# updated_sami_board_v2.net
KiCad netlist of a schematic drawn in Altium Designer
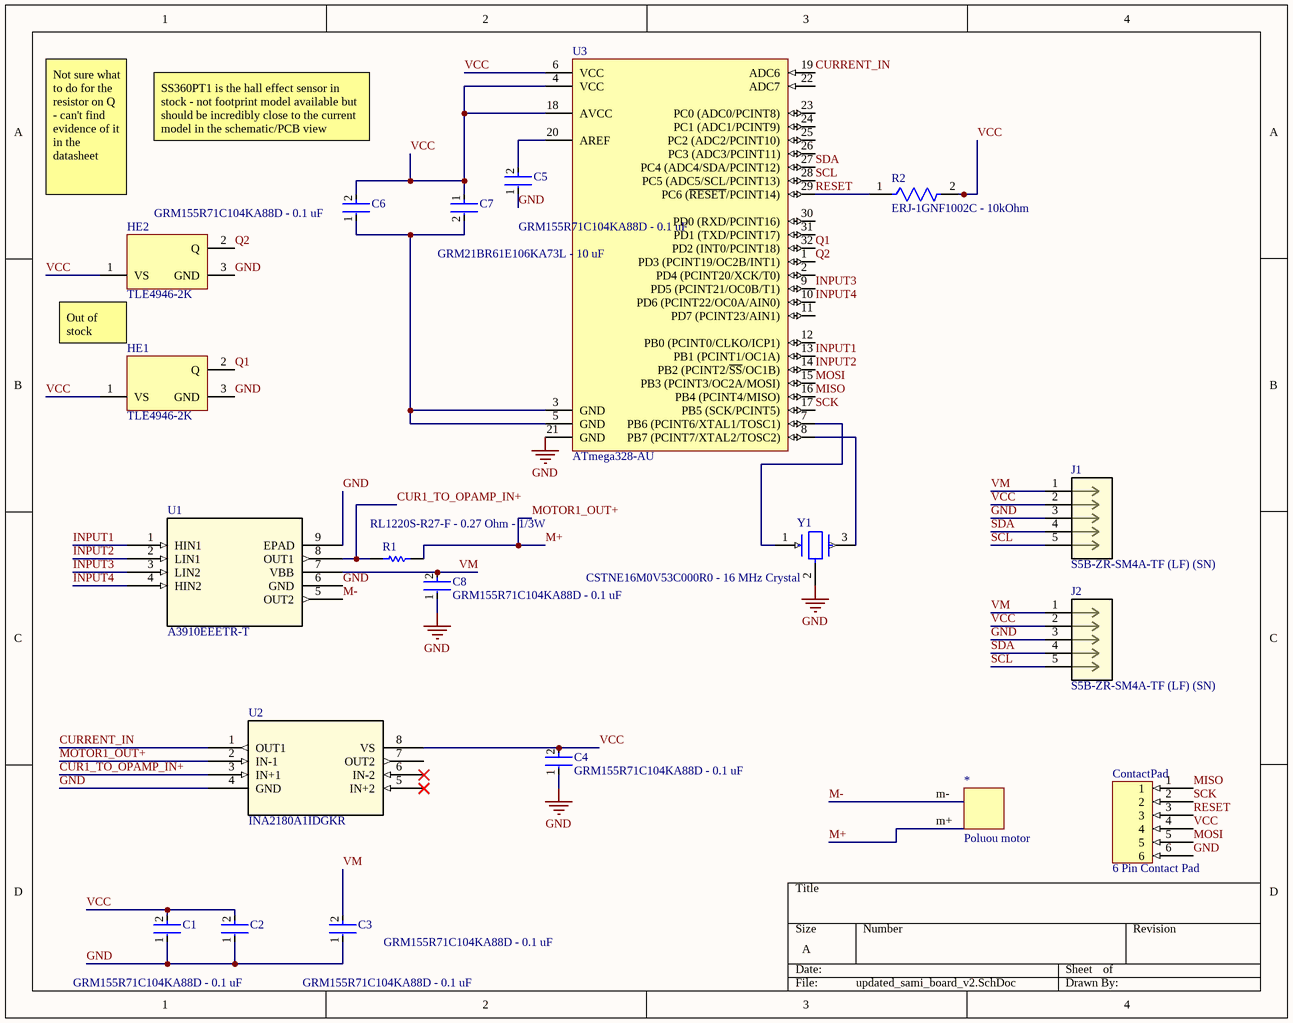
[diagram p0: updated_sami_board_v2.SchDoc]

(export (version "E")
  (design (tool "Eeschema 10.0.6"))
  (components
    (comp (ref "*")
      (value "Poluou motor")
      (footprint "PCBComponent_1")
      (libsource (lib "polulu_motor") (part "Poluou motor"))
    )
    (comp (ref "C1")
      (value "GRM155R71C104KA88D - 0.1 uF")
      (footprint "FP-GRM15-MFG")
      (description "CAP CER 0.1UF 16V X7R 0402")
      (fields (field (name "MANUFACTURER PART NUMBER") "GRM155R71C104KA88D") (field (name "TOLERANCE") "10%"))
      (libsource (lib "Altium Content Vault") (part "236180d848d6139a670b325ea6854c9"))
    )
    (comp (ref "C2")
      (value "GRM155R71C104KA88D - 0.1 uF")
      (footprint "FP-GRM15-MFG")
      (description "CAP CER 0.1UF 16V X7R 0402")
      (fields (field (name "MANUFACTURER PART NUMBER") "GRM155R71C104KA88D") (field (name "TOLERANCE") "10%"))
      (libsource (lib "Altium Content Vault") (part "236180d848d6139a670b325ea6854c9"))
    )
    (comp (ref "C3")
      (value "GRM155R71C104KA88D - 0.1 uF")
      (footprint "FP-GRM15-MFG")
      (description "CAP CER 0.1UF 16V X7R 0402")
      (fields (field (name "MANUFACTURER PART NUMBER") "GRM155R71C104KA88D") (field (name "TOLERANCE") "10%"))
      (libsource (lib "Altium Content Vault") (part "236180d848d6139a670b325ea6854c9"))
    )
    (comp (ref "C4")
      (value "GRM155R71C104KA88D - 0.1 uF")
      (footprint "FP-GRM15-MFG")
      (description "CAP CER 0.1UF 16V X7R 0402")
      (fields (field (name "MANUFACTURER PART NUMBER") "GRM155R71C104KA88D") (field (name "TOLERANCE") "10%"))
      (libsource (lib "Altium Content Vault") (part "236180d848d6139a670b325ea6854c9"))
    )
    (comp (ref "C5")
      (value "GRM155R71C104KA88D - 0.1 uF")
      (footprint "FP-GRM15-MFG")
      (description "CAP CER 0.1UF 16V X7R 0402")
      (fields (field (name "MANUFACTURER PART NUMBER") "GRM155R71C104KA88D") (field (name "TOLERANCE") "10%"))
      (libsource (lib "Altium Content Vault") (part "236180d848d6139a670b325ea6854c9"))
    )
    (comp (ref "C6")
      (value "GRM155R71C104KA88D - 0.1 uF")
      (footprint "FP-GRM15-MFG")
      (description "CAP CER 0.1UF 16V X7R 0402")
      (fields (field (name "MANUFACTURER PART NUMBER") "GRM155R71C104KA88D") (field (name "TOLERANCE") "10%"))
      (libsource (lib "Altium Content Vault") (part "236180d848d6139a670b325ea6854c9"))
    )
    (comp (ref "C7")
      (value "GRM21BR61E106KA73L - 10 uF")
      (footprint "FP-GRM21B-0_15-IPC_C")
      (description "Chip Multilayer Ceramic Capacitors for General Purpose, 0805, 10uF, X5R, 15%, 10%, 25V")
      (fields (field (name "VOLTAGE") "25V") (field (name "TOLERANCE") "10%"))
      (libsource (lib "Altium Content Vault") (part "b4654b650e69147ec39a6b967a45e02"))
    )
    (comp (ref "C8")
      (value "GRM155R71C104KA88D - 0.1 uF")
      (footprint "FP-GRM15-MFG")
      (description "CAP CER 0.1UF 16V X7R 0402")
      (fields (field (name "MANUFACTURER PART NUMBER") "GRM155R71C104KA88D") (field (name "TOLERANCE") "10%"))
      (libsource (lib "Altium Content Vault") (part "236180d848d6139a670b325ea6854c9"))
    )
    (comp (ref "ContactPad")
      (value "6 Pin Contact Pad")
      (footprint "6PinContactPad")
      (libsource (lib "6PinContactPad") (part "6 Pin Contact Pad"))
    )
    (comp (ref "HE1")
      (value "TLE4946-2K")
      (footprint "INF-PG-SC59_M")
      (description "High Precision Hall Effect Latch, PG-SC59, Reel, Green")
      (fields (field (name "MANUFACTURER") "Infineon"))
      (libsource (lib "Altium Content Vault") (part "INF-TLE49XX-SC59-3"))
    )
    (comp (ref "HE2")
      (value "TLE4946-2K")
      (footprint "INF-PG-SC59_M")
      (description "High Precision Hall Effect Latch, PG-SC59, Reel, Green")
      (fields (field (name "MANUFACTURER") "Infineon"))
      (libsource (lib "Altium Content Vault") (part "INF-TLE49XX-SC59-3"))
    )
    (comp (ref "J1")
      (value "S5B-ZR-SM4A-TF (LF) (SN)")
      (footprint "CONN_S5B-ZR-SM4A-TF_JST")
      (description "No Description Available")
      (fields (field (name "COPYRIGHT") "Copyright (C) 2021 Ultra Librarian. All rights reserved."))
      (libsource (lib "S5B-ZR-SM4A-TF_LF__SN_") (part "S5B-ZR-SM4A-TF (LF) (SN)"))
    )
    (comp (ref "J2")
      (value "S5B-ZR-SM4A-TF (LF) (SN)")
      (footprint "CONN_S5B-ZR-SM4A-TF_JST")
      (description "No Description Available")
      (fields (field (name "COPYRIGHT") "Copyright (C) 2021 Ultra Librarian. All rights reserved."))
      (libsource (lib "S5B-ZR-SM4A-TF_LF__SN_") (part "S5B-ZR-SM4A-TF (LF) (SN)"))
    )
    (comp (ref "R1")
      (value "RL1220S-R27-F - 0.27 Ohm - 1/3W")
      (footprint "RESC2013X50X40NL20T20")
      (fields (field (name "PART NUMBER") "RL1220S-R27-F") (field (name "MANUFACTURER") "Susumu"))
      (libsource (lib "Altium Content Vault") (part "RES"))
    )
    (comp (ref "R2")
      (value "ERJ-1GNF1002C - 10kOhm")
      (footprint "FP-ERJ1G-MFG")
      (description "RES SMD 10K OHM 1% 1/20W 0201")
      (fields
        (field (name "MANUFACTURER PART NUMBER") "ERJ-1GNF1002C")
        (field (name "OCTOPART") "https://octopart.com/erj-1gnf1002c-panasonic-55419697")
      )
      (libsource (lib "Altium Content Vault") (part "1029c3af85768c4190bb7ad29bc67b5"))
    )
    (comp (ref "U1")
      (value "A3910EEETR-T")
      (footprint "DFN-8_ALM")
      (description "No Description Available")
      (fields (field (name "COPYRIGHT") "Copyright (C) 2021 Ultra Librarian. All rights reserved."))
      (libsource (lib "A3910EEETR-T") (part "A3910EEETR-T"))
    )
    (comp (ref "U2")
      (value "INA2180A1IDGKR")
      (footprint "DGK8_TEX")
      (description "No Description Available")
      (fields (field (name "COPYRIGHT") "Copyright (C) 2021 Ultra Librarian. All rights reserved."))
      (libsource (lib "INA2180A1IDGKR") (part "INA2180A1IDGKR"))
    )
    (comp (ref "U3")
      (value "ATmega328-AU")
      (footprint "32A_L")
      (libsource (lib "Altium Content Vault") (part "MC-8B-ATM48-SQ32"))
    )
    (comp (ref "Y1")
      (value "CSTNE16M0V53C000R0 - 16 MHz Crystal")
      (footprint "FP-CSTNE16M0V53C000R0-MFG")
      (description "CERAMIC RES 16.0000MHZ 15PF SMD")
      (libsource (lib "Altium Content Vault") (part "7d37667f5012bb31280c8009ddd0b1c"))
    )
  )
  (nets
    (net (code "1") (name "/CUR1_TO_OPAMP_IN+") (class "Default")
      (node (ref "R1") (pin "1") (pinfunction "1_1") (pintype "passive"))
      (node (ref "U1") (pin "8") (pinfunction "OUT1_8") (pintype "output"))
      (node (ref "U2") (pin "3") (pinfunction "IN+1_3") (pintype "input"))
    )
    (net (code "2") (name "/CURRENT_IN") (class "Default")
      (node (ref "U2") (pin "1") (pinfunction "OUT1_1") (pintype "output"))
      (node (ref "U3") (pin "19") (pinfunction "ADC6_19") (pintype "input"))
    )
    (net (code "3") (name "/INPUT1") (class "Default")
      (node (ref "U1") (pin "1") (pinfunction "HIN1_1") (pintype "input"))
      (node (ref "U3") (pin "13") (pinfunction "PB1_(PCINT1/OC1A)_13") (pintype "bidirectional"))
    )
    (net (code "4") (name "/INPUT2") (class "Default")
      (node (ref "U1") (pin "2") (pinfunction "LIN1_2") (pintype "input"))
      (node (ref "U3") (pin "14") (pinfunction "PB2_(PCINT2/~{SS}/OC1B)_14") (pintype "bidirectional"))
    )
    (net (code "5") (name "/INPUT3") (class "Default")
      (node (ref "U1") (pin "3") (pinfunction "LIN2_3") (pintype "input"))
      (node (ref "U3") (pin "9") (pinfunction "PD5_(PCINT21/OC0B/T1)_9") (pintype "bidirectional"))
    )
    (net (code "6") (name "/INPUT4") (class "Default")
      (node (ref "U1") (pin "4") (pinfunction "HIN2_4") (pintype "input"))
      (node (ref "U3") (pin "10") (pinfunction "PD6_(PCINT22/OC0A/AIN0)_10") (pintype "bidirectional"))
    )
    (net (code "7") (name "/M+") (class "Default")
      (node (ref "*") (pin "m+") (pintype "passive"))
      (node (ref "R1") (pin "2") (pinfunction "2_2") (pintype "passive"))
      (node (ref "U2") (pin "2") (pinfunction "IN-1_2") (pintype "input"))
    )
    (net (code "8") (name "/M-") (class "Default")
      (node (ref "*") (pin "m-") (pintype "passive"))
      (node (ref "U1") (pin "5") (pinfunction "OUT2_5") (pintype "output"))
    )
    (net (code "9") (name "/MISO") (class "Default")
      (node (ref "ContactPad") (pin "1") (pinfunction "1_1") (pintype "input"))
      (node (ref "U3") (pin "16") (pinfunction "PB4_(PCINT4/MISO)_16") (pintype "bidirectional"))
    )
    (net (code "10") (name "/MOSI") (class "Default")
      (node (ref "ContactPad") (pin "5") (pinfunction "5_5") (pintype "input"))
      (node (ref "U3") (pin "15") (pinfunction "PB3_(PCINT3/OC2A/MOSI)_15") (pintype "bidirectional"))
    )
    (net (code "11") (name "/Q1") (class "Default")
      (node (ref "HE1") (pin "2") (pinfunction "Q_2") (pintype "open_collector"))
      (node (ref "U3") (pin "32") (pinfunction "PD2_(INT0/PCINT18)_32") (pintype "bidirectional"))
    )
    (net (code "12") (name "/Q2") (class "Default")
      (node (ref "HE2") (pin "2") (pinfunction "Q_2") (pintype "open_collector"))
      (node (ref "U3") (pin "1") (pinfunction "PD3_(PCINT19/OC2B/INT1)_1") (pintype "bidirectional"))
    )
    (net (code "13") (name "/RESET") (class "Default")
      (node (ref "ContactPad") (pin "3") (pinfunction "3_3") (pintype "input"))
      (node (ref "R2") (pin "1") (pinfunction "1_1") (pintype "passive"))
      (node (ref "U3") (pin "29") (pinfunction "PC6_(~{RESET}/PCINT14)_29") (pintype "bidirectional"))
    )
    (net (code "14") (name "/SCK") (class "Default")
      (node (ref "ContactPad") (pin "2") (pinfunction "2_2") (pintype "input"))
      (node (ref "U3") (pin "17") (pinfunction "PB5_(SCK/PCINT5)_17") (pintype "bidirectional"))
    )
    (net (code "15") (name "/SCL") (class "Default")
      (node (ref "J1") (pin "5") (pinfunction "5_5") (pintype "passive"))
      (node (ref "J2") (pin "5") (pinfunction "5_5") (pintype "passive"))
      (node (ref "U3") (pin "28") (pinfunction "PC5_(ADC5/SCL/PCINT13)_28") (pintype "bidirectional"))
    )
    (net (code "16") (name "/SDA") (class "Default")
      (node (ref "J1") (pin "4") (pinfunction "4_4") (pintype "passive"))
      (node (ref "J2") (pin "4") (pinfunction "4_4") (pintype "passive"))
      (node (ref "U3") (pin "27") (pinfunction "PC4_(ADC4/SDA/PCINT12)_27") (pintype "bidirectional"))
    )
    (net (code "17") (name "/VCC") (class "Default")
      (node (ref "C1") (pin "2") (pinfunction "2_2") (pintype "passive"))
      (node (ref "C2") (pin "2") (pinfunction "2_2") (pintype "passive"))
      (node (ref "C4") (pin "2") (pinfunction "2_2") (pintype "passive"))
      (node (ref "C6") (pin "2") (pinfunction "2_2") (pintype "passive"))
      (node (ref "C7") (pin "1") (pinfunction "1_1") (pintype "passive"))
      (node (ref "ContactPad") (pin "4") (pinfunction "4_4") (pintype "input"))
      (node (ref "HE1") (pin "1") (pinfunction "VS_1") (pintype "power_in"))
      (node (ref "HE2") (pin "1") (pinfunction "VS_1") (pintype "power_in"))
      (node (ref "J1") (pin "2") (pinfunction "2_2") (pintype "passive"))
      (node (ref "J2") (pin "2") (pinfunction "2_2") (pintype "passive"))
      (node (ref "R2") (pin "2") (pinfunction "2_2") (pintype "passive"))
      (node (ref "U2") (pin "8") (pinfunction "VS_8") (pintype "power_in"))
      (node (ref "U3") (pin "18") (pinfunction "AVCC_18") (pintype "power_in"))
      (node (ref "U3") (pin "4") (pinfunction "VCC_4") (pintype "power_in"))
      (node (ref "U3") (pin "6") (pinfunction "VCC_6") (pintype "power_in"))
    )
    (net (code "18") (name "/VM") (class "Default")
      (node (ref "C3") (pin "2") (pinfunction "2_2") (pintype "passive"))
      (node (ref "C8") (pin "2") (pinfunction "2_2") (pintype "passive"))
      (node (ref "J1") (pin "1") (pinfunction "1_1") (pintype "passive"))
      (node (ref "J2") (pin "1") (pinfunction "1_1") (pintype "passive"))
      (node (ref "U1") (pin "7") (pinfunction "VBB_7") (pintype "passive"))
    )
    (net (code "19") (name "GND") (class "Default")
      (node (ref "C1") (pin "1") (pinfunction "1_1") (pintype "passive"))
      (node (ref "C2") (pin "1") (pinfunction "1_1") (pintype "passive"))
      (node (ref "C3") (pin "1") (pinfunction "1_1") (pintype "passive"))
      (node (ref "C4") (pin "1") (pinfunction "1_1") (pintype "passive"))
      (node (ref "C5") (pin "1") (pinfunction "1_1") (pintype "passive"))
      (node (ref "C8") (pin "1") (pinfunction "1_1") (pintype "passive"))
      (node (ref "ContactPad") (pin "6") (pinfunction "6_6") (pintype "input"))
      (node (ref "HE1") (pin "3") (pinfunction "GND_3") (pintype "power_in"))
      (node (ref "HE2") (pin "3") (pinfunction "GND_3") (pintype "power_in"))
      (node (ref "J1") (pin "3") (pinfunction "3_3") (pintype "passive"))
      (node (ref "J2") (pin "3") (pinfunction "3_3") (pintype "passive"))
      (node (ref "U1") (pin "6") (pinfunction "GND_6") (pintype "passive"))
      (node (ref "U1") (pin "9") (pinfunction "EPAD_9") (pintype "passive"))
      (node (ref "U2") (pin "4") (pinfunction "GND_4") (pintype "power_in"))
      (node (ref "U3") (pin "21") (pinfunction "GND_21") (pintype "power_in"))
      (node (ref "Y1") (pin "2") (pinfunction "GND_2") (pintype "power_in"))
    )
    (net (code "20") (name "Net-(C6-Pad1)") (class "Default")
      (node (ref "C6") (pin "1") (pinfunction "1_1") (pintype "passive"))
      (node (ref "C7") (pin "2") (pinfunction "2_2") (pintype "passive"))
      (node (ref "U3") (pin "3") (pinfunction "GND_3") (pintype "power_in"))
      (node (ref "U3") (pin "5") (pinfunction "GND_5") (pintype "power_in"))
    )
    (net (code "21") (name "Net-(U3-AREF)") (class "Default")
      (node (ref "C5") (pin "2") (pinfunction "2_2") (pintype "passive"))
      (node (ref "U3") (pin "20") (pinfunction "AREF_20") (pintype "passive"))
    )
    (net (code "22") (name "Net-(U3-PB6_(PCINT6{slash}XTAL1{slash}TOSC1))") (class "Default")
      (node (ref "U3") (pin "7") (pinfunction "PB6_(PCINT6/XTAL1/TOSC1)_7") (pintype "bidirectional"))
      (node (ref "Y1") (pin "1") (pinfunction "Input_1") (pintype "input"))
    )
    (net (code "23") (name "Net-(U3-PB7_(PCINT7{slash}XTAL2{slash}TOSC2))") (class "Default")
      (node (ref "U3") (pin "8") (pinfunction "PB7_(PCINT7/XTAL2/TOSC2)_8") (pintype "bidirectional"))
      (node (ref "Y1") (pin "3") (pinfunction "Output_3") (pintype "output"))
    )
    (net (code "24") (name "unconnected-(U2-IN+2-Pad5)") (class "Default")
      (node (ref "U2") (pin "5") (pinfunction "IN+2_5") (pintype "input+no_connect"))
    )
    (net (code "25") (name "unconnected-(U2-IN-2-Pad6)") (class "Default")
      (node (ref "U2") (pin "6") (pinfunction "IN-2_6") (pintype "input+no_connect"))
    )
    (net (code "26") (name "unconnected-(U2-OUT2-Pad7)") (class "Default")
      (node (ref "U2") (pin "7") (pinfunction "OUT2_7") (pintype "output"))
    )
    (net (code "27") (name "unconnected-(U3-ADC7-Pad22)") (class "Default")
      (node (ref "U3") (pin "22") (pinfunction "ADC7_22") (pintype "input"))
    )
    (net (code "28") (name "unconnected-(U3-PB0_(PCINT0{slash}CLKO{slash}ICP1)-Pad12)") (class "Default")
      (node (ref "U3") (pin "12") (pinfunction "PB0_(PCINT0/CLKO/ICP1)_12") (pintype "bidirectional"))
    )
    (net (code "29") (name "unconnected-(U3-PC0_(ADC0{slash}PCINT8)-Pad23)") (class "Default")
      (node (ref "U3") (pin "23") (pinfunction "PC0_(ADC0/PCINT8)_23") (pintype "bidirectional"))
    )
    (net (code "30") (name "unconnected-(U3-PC1_(ADC1{slash}PCINT9)-Pad24)") (class "Default")
      (node (ref "U3") (pin "24") (pinfunction "PC1_(ADC1/PCINT9)_24") (pintype "bidirectional"))
    )
    (net (code "31") (name "unconnected-(U3-PC2_(ADC2{slash}PCINT10)-Pad25)") (class "Default")
      (node (ref "U3") (pin "25") (pinfunction "PC2_(ADC2/PCINT10)_25") (pintype "bidirectional"))
    )
    (net (code "32") (name "unconnected-(U3-PC3_(ADC3{slash}PCINT11)-Pad26)") (class "Default")
      (node (ref "U3") (pin "26") (pinfunction "PC3_(ADC3/PCINT11)_26") (pintype "bidirectional"))
    )
    (net (code "33") (name "unconnected-(U3-PD0_(RXD{slash}PCINT16)-Pad30)") (class "Default")
      (node (ref "U3") (pin "30") (pinfunction "PD0_(RXD/PCINT16)_30") (pintype "bidirectional"))
    )
    (net (code "34") (name "unconnected-(U3-PD1_(TXD{slash}PCINT17)-Pad31)") (class "Default")
      (node (ref "U3") (pin "31") (pinfunction "PD1_(TXD/PCINT17)_31") (pintype "bidirectional"))
    )
    (net (code "35") (name "unconnected-(U3-PD4_(PCINT20{slash}XCK{slash}T0)-Pad2)") (class "Default")
      (node (ref "U3") (pin "2") (pinfunction "PD4_(PCINT20/XCK/T0)_2") (pintype "bidirectional"))
    )
    (net (code "36") (name "unconnected-(U3-PD7_(PCINT23{slash}AIN1)-Pad11)") (class "Default")
      (node (ref "U3") (pin "11") (pinfunction "PD7_(PCINT23/AIN1)_11") (pintype "bidirectional"))
    )
  )
)
